# SNES-logo-base.net
KiCad netlist of a schematic drawn in EAGLE
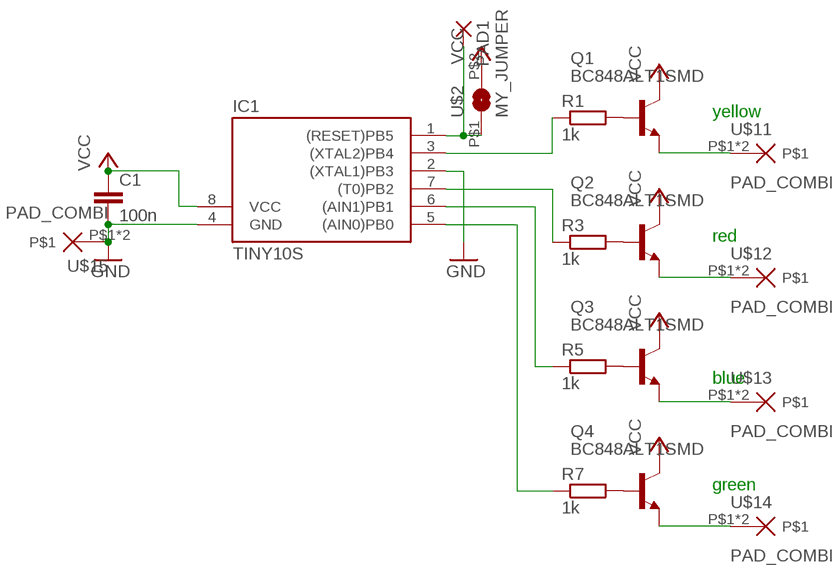
[diagram p0: schematic, sheet 1]

(export (version "E")
  (design (tool "Eeschema 10.0.6"))
  (components
    (comp (ref "C1")
      (value "100n")
      (footprint "eagle-import:Z0805")
      (libsource (lib "eagle-import") (part "C0805"))
    )
    (comp (ref "IC1")
      (value "TINY10S")
      (footprint "eagle-import:SOIC8")
      (libsource (lib "eagle-import") (part "TINY10S"))
    )
    (comp (ref "PAD1")
      (value "SMD2")
      (footprint "eagle-import:SMD1,27-2,54")
      (libsource (lib "eagle-import") (part "SMD2"))
    )
    (comp (ref "Q1")
      (value "BC848ALT1SMD")
      (footprint "eagle-import:SOT23")
      (libsource (lib "eagle-import") (part "BC848SMDALT1"))
    )
    (comp (ref "Q2")
      (value "BC848ALT1SMD")
      (footprint "eagle-import:SOT23")
      (libsource (lib "eagle-import") (part "BC848SMDALT1"))
    )
    (comp (ref "Q3")
      (value "BC848ALT1SMD")
      (footprint "eagle-import:SOT23")
      (libsource (lib "eagle-import") (part "BC848SMDALT1"))
    )
    (comp (ref "Q4")
      (value "BC848ALT1SMD")
      (footprint "eagle-import:SOT23")
      (libsource (lib "eagle-import") (part "BC848SMDALT1"))
    )
    (comp (ref "R1")
      (value "1k")
      (footprint "eagle-import:Z0805")
      (libsource (lib "eagle-import") (part "R0805"))
    )
    (comp (ref "R3")
      (value "1k")
      (footprint "eagle-import:Z0805")
      (libsource (lib "eagle-import") (part "R0805"))
    )
    (comp (ref "R5")
      (value "1k")
      (footprint "eagle-import:Z0805")
      (libsource (lib "eagle-import") (part "R0805"))
    )
    (comp (ref "R7")
      (value "1k")
      (footprint "eagle-import:Z0805")
      (libsource (lib "eagle-import") (part "R0805"))
    )
    (comp (ref "U$2")
      (value "MY_JUMPER")
      (footprint "eagle-import:MYJUMP")
      (libsource (lib "eagle-import") (part "MY_JUMPER"))
    )
    (comp (ref "U$11")
      (value "PAD_COMBI")
      (footprint "eagle-import:PAD_COMBI")
      (libsource (lib "eagle-import") (part "PAD_COMBI"))
    )
    (comp (ref "U$12")
      (value "PAD_COMBI")
      (footprint "eagle-import:PAD_COMBI")
      (libsource (lib "eagle-import") (part "PAD_COMBI"))
    )
    (comp (ref "U$13")
      (value "PAD_COMBI")
      (footprint "eagle-import:PAD_COMBI")
      (libsource (lib "eagle-import") (part "PAD_COMBI"))
    )
    (comp (ref "U$14")
      (value "PAD_COMBI")
      (footprint "eagle-import:PAD_COMBI")
      (libsource (lib "eagle-import") (part "PAD_COMBI"))
    )
    (comp (ref "U$15")
      (value "PAD_COMBI")
      (footprint "eagle-import:PAD_COMBI")
      (libsource (lib "eagle-import") (part "PAD_COMBI"))
    )
  )
  (nets
    (net (code "1") (name "GND") (class "Default")
      (node (ref "C1") (pin "2") (pinfunction "2_2") (pintype "passive"))
      (node (ref "IC1") (pin "2") (pinfunction "(XTAL1)PB3_2") (pintype "bidirectional"))
      (node (ref "IC1") (pin "4") (pinfunction "GND_4") (pintype "power_in"))
      (node (ref "U$15") (pin "P$1") (pinfunction "P$1_P$1") (pintype "bidirectional"))
      (node (ref "U$15") (pin "P$2") (pinfunction "P$1_P$2") (pintype "bidirectional"))
    )
    (net (code "2") (name "Net-(IC1-(AIN0)PB0)") (class "Default")
      (node (ref "IC1") (pin "5") (pinfunction "(AIN0)PB0_5") (pintype "bidirectional"))
      (node (ref "R7") (pin "1") (pinfunction "1_1") (pintype "passive"))
    )
    (net (code "3") (name "Net-(IC1-(AIN1)PB1)") (class "Default")
      (node (ref "IC1") (pin "6") (pinfunction "(AIN1)PB1_6") (pintype "bidirectional"))
      (node (ref "R5") (pin "1") (pinfunction "1_1") (pintype "passive"))
    )
    (net (code "4") (name "Net-(IC1-(RESET)PB5)") (class "Default")
      (node (ref "IC1") (pin "1") (pinfunction "(RESET)PB5_1") (pintype "bidirectional"))
      (node (ref "PAD1") (pin "1") (pinfunction "P_1") (pintype "passive"))
      (node (ref "U$2") (pin "P$1") (pinfunction "1_P$1") (pintype "passive"))
    )
    (net (code "5") (name "Net-(IC1-(T0)PB2)") (class "Default")
      (node (ref "IC1") (pin "7") (pinfunction "(T0)PB2_7") (pintype "bidirectional"))
      (node (ref "R3") (pin "1") (pinfunction "1_1") (pintype "passive"))
    )
    (net (code "6") (name "Net-(IC1-(XTAL2)PB4)") (class "Default")
      (node (ref "IC1") (pin "3") (pinfunction "(XTAL2)PB4_3") (pintype "bidirectional"))
      (node (ref "R1") (pin "1") (pinfunction "1_1") (pintype "passive"))
    )
    (net (code "7") (name "Net-(Q1-B)") (class "Default")
      (node (ref "Q1") (pin "1") (pinfunction "B_1") (pintype "passive"))
      (node (ref "R1") (pin "2") (pinfunction "2_2") (pintype "passive"))
    )
    (net (code "8") (name "Net-(Q1-E)") (class "Default")
      (node (ref "Q1") (pin "2") (pinfunction "E_2") (pintype "passive"))
      (node (ref "U$11") (pin "P$1") (pinfunction "P$1_P$1") (pintype "bidirectional"))
      (node (ref "U$11") (pin "P$2") (pinfunction "P$1_P$2") (pintype "bidirectional"))
    )
    (net (code "9") (name "Net-(Q2-B)") (class "Default")
      (node (ref "Q2") (pin "1") (pinfunction "B_1") (pintype "passive"))
      (node (ref "R3") (pin "2") (pinfunction "2_2") (pintype "passive"))
    )
    (net (code "10") (name "Net-(Q2-E)") (class "Default")
      (node (ref "Q2") (pin "2") (pinfunction "E_2") (pintype "passive"))
      (node (ref "U$12") (pin "P$1") (pinfunction "P$1_P$1") (pintype "bidirectional"))
      (node (ref "U$12") (pin "P$2") (pinfunction "P$1_P$2") (pintype "bidirectional"))
    )
    (net (code "11") (name "Net-(Q3-B)") (class "Default")
      (node (ref "Q3") (pin "1") (pinfunction "B_1") (pintype "passive"))
      (node (ref "R5") (pin "2") (pinfunction "2_2") (pintype "passive"))
    )
    (net (code "12") (name "Net-(Q3-E)") (class "Default")
      (node (ref "Q3") (pin "2") (pinfunction "E_2") (pintype "passive"))
      (node (ref "U$13") (pin "P$1") (pinfunction "P$1_P$1") (pintype "bidirectional"))
      (node (ref "U$13") (pin "P$2") (pinfunction "P$1_P$2") (pintype "bidirectional"))
    )
    (net (code "13") (name "Net-(Q4-B)") (class "Default")
      (node (ref "Q4") (pin "1") (pinfunction "B_1") (pintype "passive"))
      (node (ref "R7") (pin "2") (pinfunction "2_2") (pintype "passive"))
    )
    (net (code "14") (name "Net-(Q4-E)") (class "Default")
      (node (ref "Q4") (pin "2") (pinfunction "E_2") (pintype "passive"))
      (node (ref "U$14") (pin "P$1") (pinfunction "P$1_P$1") (pintype "bidirectional"))
      (node (ref "U$14") (pin "P$2") (pinfunction "P$1_P$2") (pintype "bidirectional"))
    )
    (net (code "15") (name "VCC") (class "Default")
      (node (ref "C1") (pin "1") (pinfunction "1_1") (pintype "passive"))
      (node (ref "IC1") (pin "8") (pinfunction "VCC_8") (pintype "power_in"))
      (node (ref "Q1") (pin "3") (pinfunction "C_3") (pintype "passive"))
      (node (ref "Q2") (pin "3") (pinfunction "C_3") (pintype "passive"))
      (node (ref "Q3") (pin "3") (pinfunction "C_3") (pintype "passive"))
      (node (ref "Q4") (pin "3") (pinfunction "C_3") (pintype "passive"))
      (node (ref "U$2") (pin "P$2") (pinfunction "2_P$2") (pintype "passive"))
    )
  )
)
